# Layout.net
KiCad netlist of a schematic drawn in EAGLE
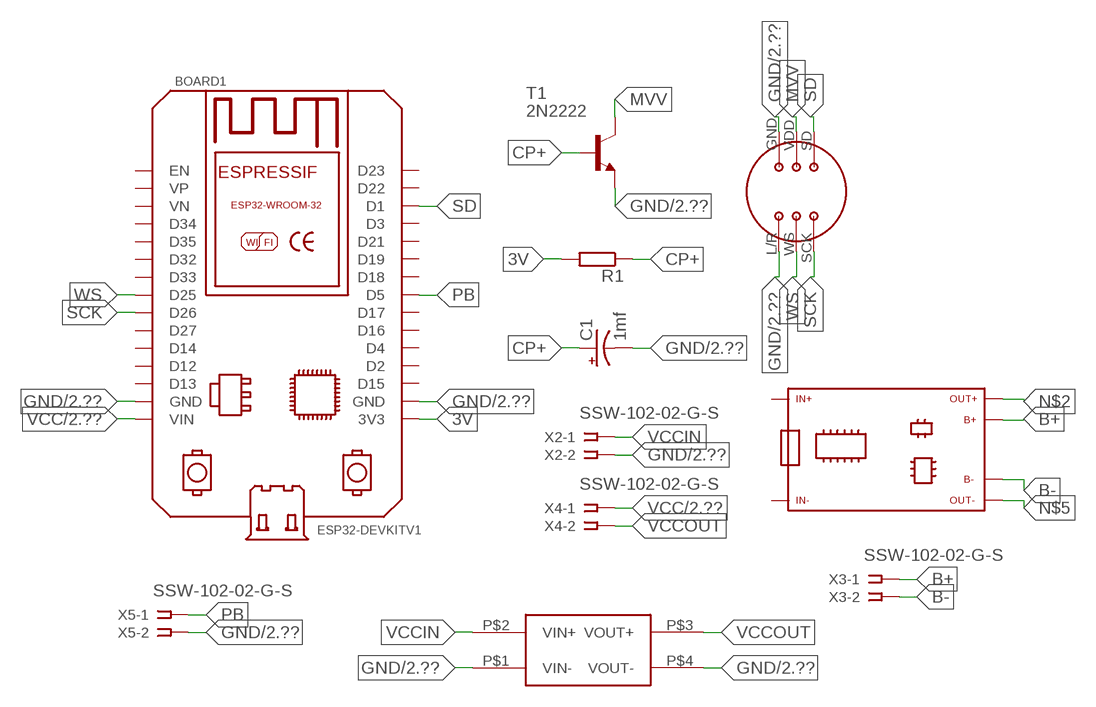
[diagram p0: schematic, sheet 1]
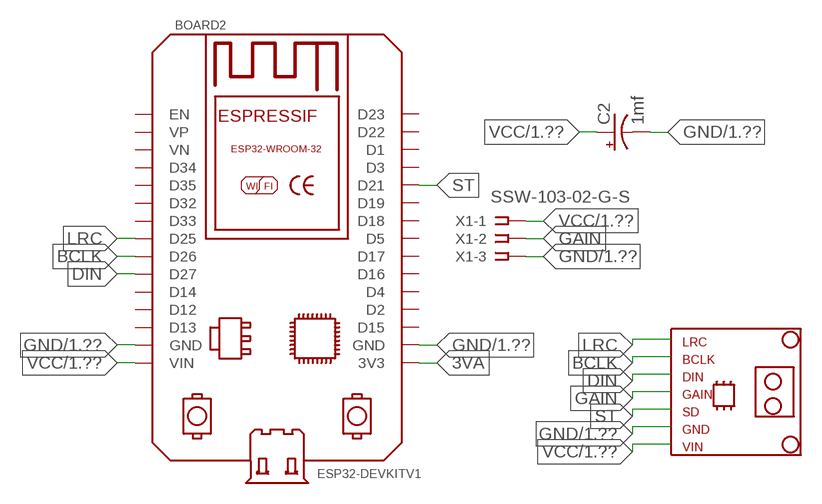
[diagram p1: schematic, sheet 2]

(export (version "E")
  (design (tool "Eeschema 10.0.6"))
  (components
    (comp (ref "BOARD1")
      (value "ESP32DEVKITV1")
      (footprint "eagle-import:ESP32-DEVKITV1")
      (libsource (lib "eagle-import") (part "ESP32DEVKITV1"))
    )
    (comp (ref "C1")
      (value "1mf")
      (footprint "eagle-import:CPOL-RADIAL-5MM-10MM-KIT")
      (libsource (lib "eagle-import") (part "1000UF-RADIAL-5MM-35V-20%-KIT"))
    )
    (comp (ref "CHARGER_HW-1")
      (value "CHARGER_HW-107")
      (footprint "eagle-import:CHARGER_HW-107")
      (libsource (lib "eagle-import") (part "CHARGER_HW-107"))
    )
    (comp (ref "INMP1")
      (value "INMP441")
      (footprint "eagle-import:INMP441")
      (libsource (lib "eagle-import") (part "INMP441"))
    )
    (comp (ref "R1")
      (value "R-EU_0204/7")
      (footprint "eagle-import:0204_7")
      (libsource (lib "eagle-import") (part "R-EU_0204/7"))
    )
    (comp (ref "T1")
      (value "2N2222")
      (footprint "eagle-import:TO18")
      (libsource (lib "eagle-import") (part "2N2222"))
    )
    (comp (ref "U$2")
      (value "MP1584-MINI-SMD")
      (footprint "eagle-import:MINI-DC-BRICK-SMD")
      (libsource (lib "eagle-import") (part "MP1584-MINI-SMD"))
    )
    (comp (ref "X2")
      (value "SSW-102-02-G-S")
      (footprint "eagle-import:SSW-102-02-G-S")
      (fields (field (name "MF") "Samtec Inc."))
      (libsource (lib "eagle-import") (part "SSW-102-02-G-S"))
    )
    (comp (ref "X3")
      (value "SSW-102-02-G-S")
      (footprint "eagle-import:SSW-102-02-G-S")
      (fields (field (name "MF") "Samtec Inc."))
      (libsource (lib "eagle-import") (part "SSW-102-02-G-S"))
    )
    (comp (ref "X4")
      (value "SSW-102-02-G-S")
      (footprint "eagle-import:SSW-102-02-G-S")
      (fields (field (name "MF") "Samtec Inc."))
      (libsource (lib "eagle-import") (part "SSW-102-02-G-S"))
    )
    (comp (ref "X5")
      (value "SSW-102-02-G-S")
      (footprint "eagle-import:SSW-102-02-G-S")
      (fields (field (name "MF") "Samtec Inc."))
      (libsource (lib "eagle-import") (part "SSW-102-02-G-S"))
    )
    (comp (ref "BOARD2")
      (value "ESP32DEVKITV1")
      (footprint "eagle-import:ESP32-DEVKITV1")
      (libsource (lib "eagle-import") (part "ESP32DEVKITV1"))
    )
    (comp (ref "C2")
      (value "1mf")
      (footprint "eagle-import:CPOL-RADIAL-5MM-10MM-KIT")
      (libsource (lib "eagle-import") (part "1000UF-RADIAL-5MM-35V-20%-KIT"))
    )
    (comp (ref "MAX98357A1")
      (value "MAX98357A")
      (footprint "eagle-import:MAX98357A")
      (libsource (lib "eagle-import") (part "MAX98357A"))
    )
    (comp (ref "X1")
      (value "SSW-103-02-G-S")
      (footprint "eagle-import:SSW-103-02-G-S")
      (fields (field (name "MF") "Samtec Inc."))
      (libsource (lib "eagle-import") (part "SSW-103-02-G-S"))
    )
  )
  (nets
    (net (code "1") (name "3V") (class "Default")
      (node (ref "BOARD1") (pin "3V3") (pinfunction "3V3_3V3") (pintype "bidirectional"))
      (node (ref "R1") (pin "2") (pinfunction "2_2") (pintype "passive"))
    )
    (net (code "2") (name "3VA") (class "Default")
      (node (ref "BOARD2") (pin "3V3") (pinfunction "3V3_3V3") (pintype "bidirectional"))
    )
    (net (code "3") (name "B+") (class "Default")
      (node (ref "CHARGER_HW-1") (pin "B+") (pinfunction "B+_B+") (pintype "bidirectional"))
      (node (ref "X3") (pin "1") (pinfunction "1_1") (pintype "passive"))
    )
    (net (code "4") (name "B-") (class "Default")
      (node (ref "CHARGER_HW-1") (pin "B-") (pinfunction "B-_B-") (pintype "bidirectional"))
      (node (ref "X3") (pin "2") (pinfunction "1_2") (pintype "passive"))
    )
    (net (code "5") (name "BCLK") (class "Default")
      (node (ref "BOARD2") (pin "D26") (pinfunction "D26_D26") (pintype "bidirectional"))
      (node (ref "MAX98357A1") (pin "BCLK") (pinfunction "BCLK_BCLK") (pintype "bidirectional"))
    )
    (net (code "6") (name "CP+") (class "Default")
      (node (ref "C1") (pin "+") (pinfunction "+_+") (pintype "passive"))
      (node (ref "R1") (pin "1") (pinfunction "1_1") (pintype "passive"))
      (node (ref "T1") (pin "2") (pinfunction "B_2") (pintype "passive"))
    )
    (net (code "7") (name "DIN") (class "Default")
      (node (ref "BOARD2") (pin "D27") (pinfunction "D27_D27") (pintype "bidirectional"))
      (node (ref "MAX98357A1") (pin "DIN") (pinfunction "DIN_DIN") (pintype "bidirectional"))
    )
    (net (code "8") (name "GAIN") (class "Default")
      (node (ref "MAX98357A1") (pin "GAIN") (pinfunction "GAIN_GAIN") (pintype "bidirectional"))
      (node (ref "X1") (pin "2") (pinfunction "1_2") (pintype "passive"))
    )
    (net (code "9") (name "GND") (class "Default")
      (node (ref "BOARD1") (pin "GND") (pinfunction "GND_GND") (pintype "bidirectional"))
      (node (ref "BOARD1") (pin "GND@1") (pinfunction "GND_GND@1") (pintype "bidirectional"))
      (node (ref "BOARD2") (pin "GND") (pinfunction "GND_GND") (pintype "bidirectional"))
      (node (ref "BOARD2") (pin "GND@1") (pinfunction "GND_GND@1") (pintype "bidirectional"))
      (node (ref "C1") (pin "-") (pinfunction "-_-") (pintype "passive"))
      (node (ref "C2") (pin "-") (pinfunction "-_-") (pintype "passive"))
      (node (ref "INMP1") (pin "GND") (pinfunction "GND_GND") (pintype "bidirectional"))
      (node (ref "INMP1") (pin "L/R") (pinfunction "L/R_L/R") (pintype "bidirectional"))
      (node (ref "MAX98357A1") (pin "GND") (pinfunction "GND_GND") (pintype "bidirectional"))
      (node (ref "T1") (pin "1") (pinfunction "E_1") (pintype "passive"))
      (node (ref "U$2") (pin "P$1") (pinfunction "VIN-_P$1") (pintype "input"))
      (node (ref "U$2") (pin "P$4") (pinfunction "VOUT-_P$4") (pintype "output"))
      (node (ref "X1") (pin "3") (pinfunction "1_3") (pintype "passive"))
      (node (ref "X2") (pin "2") (pinfunction "1_2") (pintype "passive"))
      (node (ref "X5") (pin "2") (pinfunction "1_2") (pintype "passive"))
    )
    (net (code "10") (name "LRC") (class "Default")
      (node (ref "BOARD2") (pin "D25") (pinfunction "D25_D25") (pintype "bidirectional"))
      (node (ref "MAX98357A1") (pin "LRC") (pinfunction "LRC_LRC") (pintype "bidirectional"))
    )
    (net (code "11") (name "MVV") (class "Default")
      (node (ref "INMP1") (pin "VDD") (pinfunction "VDD_VDD") (pintype "bidirectional"))
      (node (ref "T1") (pin "3") (pinfunction "C_3") (pintype "passive"))
    )
    (net (code "12") (name "N$2") (class "Default")
      (node (ref "CHARGER_HW-1") (pin "OUT+") (pinfunction "OUT+_OUT+") (pintype "bidirectional"))
    )
    (net (code "13") (name "N$5") (class "Default")
      (node (ref "CHARGER_HW-1") (pin "OUT-") (pinfunction "OUT-_OUT-") (pintype "bidirectional"))
    )
    (net (code "14") (name "PB") (class "Default")
      (node (ref "BOARD1") (pin "D5") (pinfunction "D5_D5") (pintype "bidirectional"))
      (node (ref "X5") (pin "1") (pinfunction "1_1") (pintype "passive"))
    )
    (net (code "15") (name "SCK") (class "Default")
      (node (ref "BOARD1") (pin "D26") (pinfunction "D26_D26") (pintype "bidirectional"))
      (node (ref "INMP1") (pin "SCK") (pinfunction "SCK_SCK") (pintype "bidirectional"))
    )
    (net (code "16") (name "SD") (class "Default")
      (node (ref "BOARD1") (pin "D1") (pinfunction "D1_D1") (pintype "bidirectional"))
      (node (ref "INMP1") (pin "SD") (pinfunction "SD_SD") (pintype "bidirectional"))
    )
    (net (code "17") (name "ST") (class "Default")
      (node (ref "BOARD2") (pin "D21") (pinfunction "D21_D21") (pintype "bidirectional"))
      (node (ref "MAX98357A1") (pin "SD") (pinfunction "SD_SD") (pintype "bidirectional"))
    )
    (net (code "18") (name "VCC") (class "Default")
      (node (ref "BOARD1") (pin "VIN") (pinfunction "VIN_VIN") (pintype "bidirectional"))
      (node (ref "BOARD2") (pin "VIN") (pinfunction "VIN_VIN") (pintype "bidirectional"))
      (node (ref "C2") (pin "+") (pinfunction "+_+") (pintype "passive"))
      (node (ref "MAX98357A1") (pin "VIN") (pinfunction "VIN_VIN") (pintype "bidirectional"))
      (node (ref "X1") (pin "1") (pinfunction "1_1") (pintype "passive"))
      (node (ref "X4") (pin "1") (pinfunction "1_1") (pintype "passive"))
    )
    (net (code "19") (name "VCCIN") (class "Default")
      (node (ref "U$2") (pin "P$2") (pinfunction "VIN+_P$2") (pintype "input"))
      (node (ref "X2") (pin "1") (pinfunction "1_1") (pintype "passive"))
    )
    (net (code "20") (name "VCCOUT") (class "Default")
      (node (ref "U$2") (pin "P$3") (pinfunction "VOUT+_P$3") (pintype "output"))
      (node (ref "X4") (pin "2") (pinfunction "1_2") (pintype "passive"))
    )
    (net (code "21") (name "WS") (class "Default")
      (node (ref "BOARD1") (pin "D25") (pinfunction "D25_D25") (pintype "bidirectional"))
      (node (ref "INMP1") (pin "WS") (pinfunction "WS_WS") (pintype "bidirectional"))
    )
    (net (code "22") (name "unconnected-(BOARD1-PadD2)") (class "Default")
      (node (ref "BOARD1") (pin "D2") (pinfunction "D2_D2") (pintype "bidirectional"))
    )
    (net (code "23") (name "unconnected-(BOARD1-PadD3)") (class "Default")
      (node (ref "BOARD1") (pin "D3") (pinfunction "D3_D3") (pintype "bidirectional"))
    )
    (net (code "24") (name "unconnected-(BOARD1-PadD4)") (class "Default")
      (node (ref "BOARD1") (pin "D4") (pinfunction "D4_D4") (pintype "bidirectional"))
    )
    (net (code "25") (name "unconnected-(BOARD1-PadD12)") (class "Default")
      (node (ref "BOARD1") (pin "D12") (pinfunction "D12_D12") (pintype "bidirectional"))
    )
    (net (code "26") (name "unconnected-(BOARD1-PadD13)") (class "Default")
      (node (ref "BOARD1") (pin "D13") (pinfunction "D13_D13") (pintype "bidirectional"))
    )
    (net (code "27") (name "unconnected-(BOARD1-PadD14)") (class "Default")
      (node (ref "BOARD1") (pin "D14") (pinfunction "D14_D14") (pintype "bidirectional"))
    )
    (net (code "28") (name "unconnected-(BOARD1-PadD15)") (class "Default")
      (node (ref "BOARD1") (pin "D15") (pinfunction "D15_D15") (pintype "bidirectional"))
    )
    (net (code "29") (name "unconnected-(BOARD1-PadD16)") (class "Default")
      (node (ref "BOARD1") (pin "D16") (pinfunction "D16_D16") (pintype "bidirectional"))
    )
    (net (code "30") (name "unconnected-(BOARD1-PadD17)") (class "Default")
      (node (ref "BOARD1") (pin "D17") (pinfunction "D17_D17") (pintype "bidirectional"))
    )
    (net (code "31") (name "unconnected-(BOARD1-PadD18)") (class "Default")
      (node (ref "BOARD1") (pin "D18") (pinfunction "D18_D18") (pintype "bidirectional"))
    )
    (net (code "32") (name "unconnected-(BOARD1-PadD19)") (class "Default")
      (node (ref "BOARD1") (pin "D19") (pinfunction "D19_D19") (pintype "bidirectional"))
    )
    (net (code "33") (name "unconnected-(BOARD1-PadD21)") (class "Default")
      (node (ref "BOARD1") (pin "D21") (pinfunction "D21_D21") (pintype "bidirectional"))
    )
    (net (code "34") (name "unconnected-(BOARD1-PadD22)") (class "Default")
      (node (ref "BOARD1") (pin "D22") (pinfunction "D22_D22") (pintype "bidirectional"))
    )
    (net (code "35") (name "unconnected-(BOARD1-PadD23)") (class "Default")
      (node (ref "BOARD1") (pin "D23") (pinfunction "D23_D23") (pintype "bidirectional"))
    )
    (net (code "36") (name "unconnected-(BOARD1-PadD27)") (class "Default")
      (node (ref "BOARD1") (pin "D27") (pinfunction "D27_D27") (pintype "bidirectional"))
    )
    (net (code "37") (name "unconnected-(BOARD1-PadD32)") (class "Default")
      (node (ref "BOARD1") (pin "D32") (pinfunction "D32_D32") (pintype "bidirectional"))
    )
    (net (code "38") (name "unconnected-(BOARD1-PadD33)") (class "Default")
      (node (ref "BOARD1") (pin "D33") (pinfunction "D33_D33") (pintype "bidirectional"))
    )
    (net (code "39") (name "unconnected-(BOARD1-PadD34)") (class "Default")
      (node (ref "BOARD1") (pin "D34") (pinfunction "D34_D34") (pintype "bidirectional"))
    )
    (net (code "40") (name "unconnected-(BOARD1-PadD35)") (class "Default")
      (node (ref "BOARD1") (pin "D35") (pinfunction "D35_D35") (pintype "bidirectional"))
    )
    (net (code "41") (name "unconnected-(BOARD1-PadEN)") (class "Default")
      (node (ref "BOARD1") (pin "EN") (pinfunction "EN_EN") (pintype "bidirectional"))
    )
    (net (code "42") (name "unconnected-(BOARD1-PadVN)") (class "Default")
      (node (ref "BOARD1") (pin "VN") (pinfunction "VN_VN") (pintype "bidirectional"))
    )
    (net (code "43") (name "unconnected-(BOARD1-PadVP)") (class "Default")
      (node (ref "BOARD1") (pin "VP") (pinfunction "VP_VP") (pintype "bidirectional"))
    )
    (net (code "44") (name "unconnected-(BOARD2-PadD1)") (class "Default")
      (node (ref "BOARD2") (pin "D1") (pinfunction "D1_D1") (pintype "bidirectional"))
    )
    (net (code "45") (name "unconnected-(BOARD2-PadD2)") (class "Default")
      (node (ref "BOARD2") (pin "D2") (pinfunction "D2_D2") (pintype "bidirectional"))
    )
    (net (code "46") (name "unconnected-(BOARD2-PadD3)") (class "Default")
      (node (ref "BOARD2") (pin "D3") (pinfunction "D3_D3") (pintype "bidirectional"))
    )
    (net (code "47") (name "unconnected-(BOARD2-PadD4)") (class "Default")
      (node (ref "BOARD2") (pin "D4") (pinfunction "D4_D4") (pintype "bidirectional"))
    )
    (net (code "48") (name "unconnected-(BOARD2-PadD5)") (class "Default")
      (node (ref "BOARD2") (pin "D5") (pinfunction "D5_D5") (pintype "bidirectional"))
    )
    (net (code "49") (name "unconnected-(BOARD2-PadD12)") (class "Default")
      (node (ref "BOARD2") (pin "D12") (pinfunction "D12_D12") (pintype "bidirectional"))
    )
    (net (code "50") (name "unconnected-(BOARD2-PadD13)") (class "Default")
      (node (ref "BOARD2") (pin "D13") (pinfunction "D13_D13") (pintype "bidirectional"))
    )
    (net (code "51") (name "unconnected-(BOARD2-PadD14)") (class "Default")
      (node (ref "BOARD2") (pin "D14") (pinfunction "D14_D14") (pintype "bidirectional"))
    )
    (net (code "52") (name "unconnected-(BOARD2-PadD15)") (class "Default")
      (node (ref "BOARD2") (pin "D15") (pinfunction "D15_D15") (pintype "bidirectional"))
    )
    (net (code "53") (name "unconnected-(BOARD2-PadD16)") (class "Default")
      (node (ref "BOARD2") (pin "D16") (pinfunction "D16_D16") (pintype "bidirectional"))
    )
    (net (code "54") (name "unconnected-(BOARD2-PadD17)") (class "Default")
      (node (ref "BOARD2") (pin "D17") (pinfunction "D17_D17") (pintype "bidirectional"))
    )
    (net (code "55") (name "unconnected-(BOARD2-PadD18)") (class "Default")
      (node (ref "BOARD2") (pin "D18") (pinfunction "D18_D18") (pintype "bidirectional"))
    )
    (net (code "56") (name "unconnected-(BOARD2-PadD19)") (class "Default")
      (node (ref "BOARD2") (pin "D19") (pinfunction "D19_D19") (pintype "bidirectional"))
    )
    (net (code "57") (name "unconnected-(BOARD2-PadD22)") (class "Default")
      (node (ref "BOARD2") (pin "D22") (pinfunction "D22_D22") (pintype "bidirectional"))
    )
    (net (code "58") (name "unconnected-(BOARD2-PadD23)") (class "Default")
      (node (ref "BOARD2") (pin "D23") (pinfunction "D23_D23") (pintype "bidirectional"))
    )
    (net (code "59") (name "unconnected-(BOARD2-PadD32)") (class "Default")
      (node (ref "BOARD2") (pin "D32") (pinfunction "D32_D32") (pintype "bidirectional"))
    )
    (net (code "60") (name "unconnected-(BOARD2-PadD33)") (class "Default")
      (node (ref "BOARD2") (pin "D33") (pinfunction "D33_D33") (pintype "bidirectional"))
    )
    (net (code "61") (name "unconnected-(BOARD2-PadD34)") (class "Default")
      (node (ref "BOARD2") (pin "D34") (pinfunction "D34_D34") (pintype "bidirectional"))
    )
    (net (code "62") (name "unconnected-(BOARD2-PadD35)") (class "Default")
      (node (ref "BOARD2") (pin "D35") (pinfunction "D35_D35") (pintype "bidirectional"))
    )
    (net (code "63") (name "unconnected-(BOARD2-PadEN)") (class "Default")
      (node (ref "BOARD2") (pin "EN") (pinfunction "EN_EN") (pintype "bidirectional"))
    )
    (net (code "64") (name "unconnected-(BOARD2-PadVN)") (class "Default")
      (node (ref "BOARD2") (pin "VN") (pinfunction "VN_VN") (pintype "bidirectional"))
    )
    (net (code "65") (name "unconnected-(BOARD2-PadVP)") (class "Default")
      (node (ref "BOARD2") (pin "VP") (pinfunction "VP_VP") (pintype "bidirectional"))
    )
    (net (code "66") (name "unconnected-(CHARGER_HW-1-PadIN+)") (class "Default")
      (node (ref "CHARGER_HW-1") (pin "IN+") (pinfunction "IN+_IN+") (pintype "bidirectional"))
    )
    (net (code "67") (name "unconnected-(CHARGER_HW-1-PadIN-)") (class "Default")
      (node (ref "CHARGER_HW-1") (pin "IN-") (pinfunction "IN-_IN-") (pintype "bidirectional"))
    )
  )
)
